# 5_viper_eagle_modern_swleds.net
KiCad netlist of a schematic drawn in Altium Designer
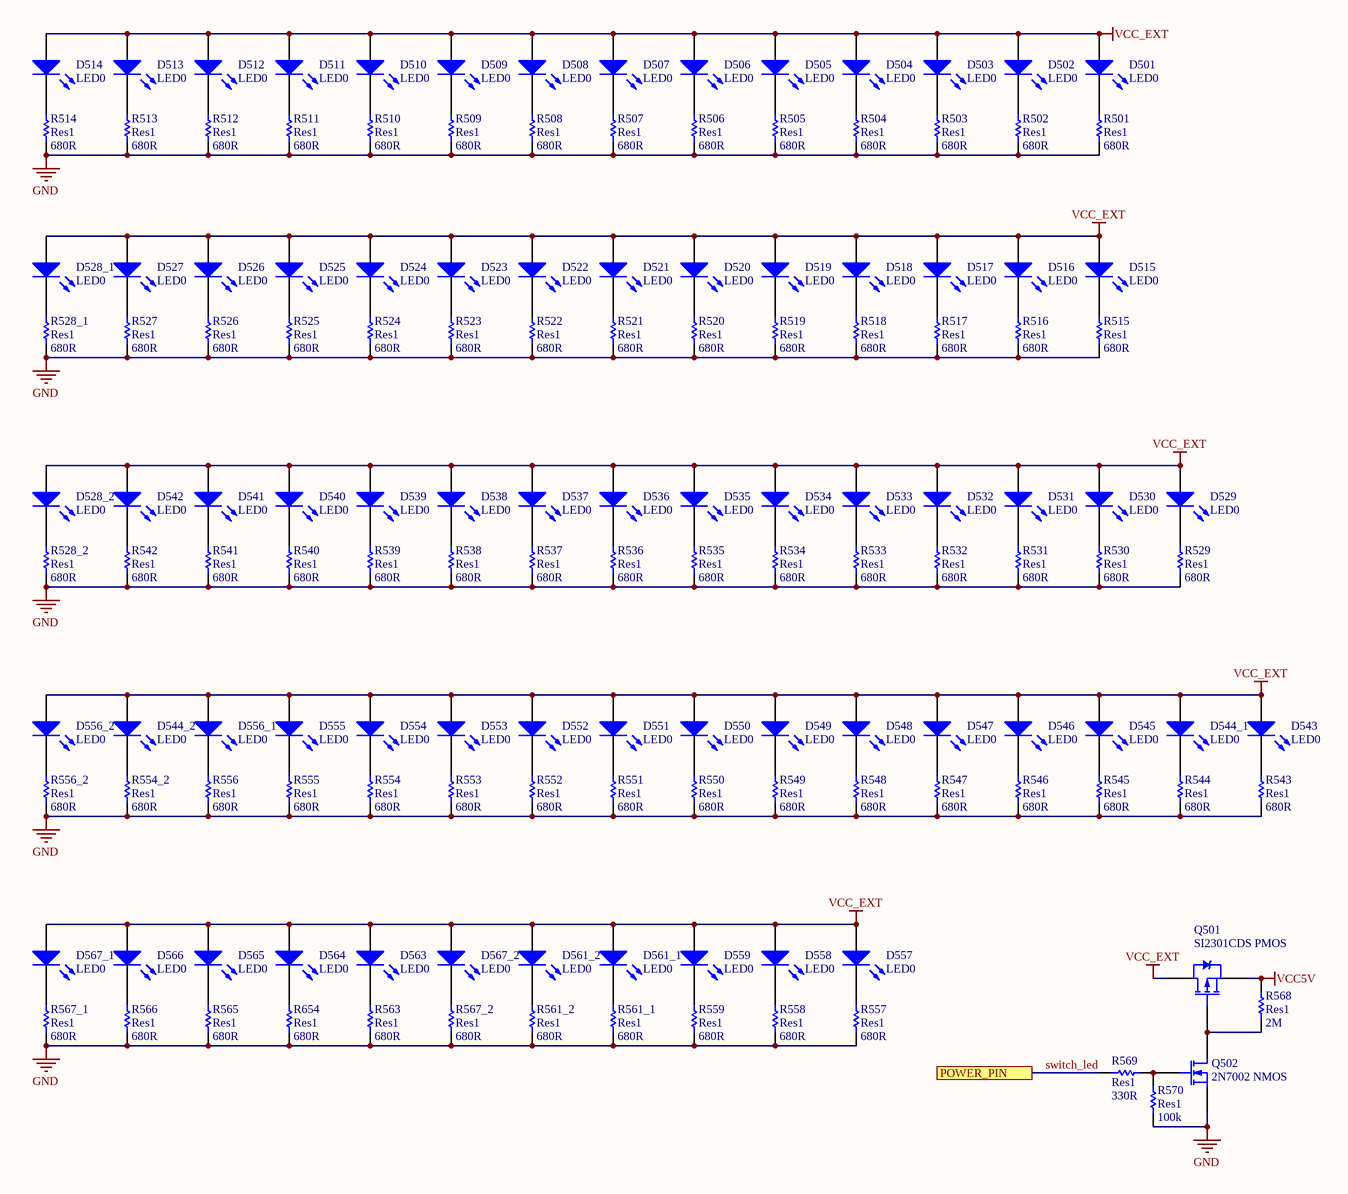
[diagram p0: 5_viper_eagle_modern_swleds.SchDoc]

(export (version "E")
  (design (tool "Eeschema 10.0.6"))
  (components
    (comp (ref "D501")
      (value "LED0")
      (footprint "MX-switch - LED")
      (description "Typical INFRARED GaAs LED")
      (libsource (lib "Miscellaneous Devices") (part "LED0"))
    )
    (comp (ref "D502")
      (value "LED0")
      (footprint "MX-switch - LED")
      (description "Typical INFRARED GaAs LED")
      (libsource (lib "Miscellaneous Devices") (part "LED0"))
    )
    (comp (ref "D503")
      (value "LED0")
      (footprint "MX-switch - LED")
      (description "Typical INFRARED GaAs LED")
      (libsource (lib "Miscellaneous Devices") (part "LED0"))
    )
    (comp (ref "D504")
      (value "LED0")
      (footprint "MX-switch - LED")
      (description "Typical INFRARED GaAs LED")
      (libsource (lib "Miscellaneous Devices") (part "LED0"))
    )
    (comp (ref "D505")
      (value "LED0")
      (footprint "MX-switch - LED")
      (description "Typical INFRARED GaAs LED")
      (libsource (lib "Miscellaneous Devices") (part "LED0"))
    )
    (comp (ref "D506")
      (value "LED0")
      (footprint "MX-switch - LED")
      (description "Typical INFRARED GaAs LED")
      (libsource (lib "Miscellaneous Devices") (part "LED0"))
    )
    (comp (ref "D507")
      (value "LED0")
      (footprint "MX-switch - LED")
      (description "Typical INFRARED GaAs LED")
      (libsource (lib "Miscellaneous Devices") (part "LED0"))
    )
    (comp (ref "D508")
      (value "LED0")
      (footprint "MX-switch - LED")
      (description "Typical INFRARED GaAs LED")
      (libsource (lib "Miscellaneous Devices") (part "LED0"))
    )
    (comp (ref "D509")
      (value "LED0")
      (footprint "MX-switch - LED")
      (description "Typical INFRARED GaAs LED")
      (libsource (lib "Miscellaneous Devices") (part "LED0"))
    )
    (comp (ref "D510")
      (value "LED0")
      (footprint "MX-switch - LED")
      (description "Typical INFRARED GaAs LED")
      (libsource (lib "Miscellaneous Devices") (part "LED0"))
    )
    (comp (ref "D511")
      (value "LED0")
      (footprint "MX-switch - LED")
      (description "Typical INFRARED GaAs LED")
      (libsource (lib "Miscellaneous Devices") (part "LED0"))
    )
    (comp (ref "D512")
      (value "LED0")
      (footprint "MX-switch - LED")
      (description "Typical INFRARED GaAs LED")
      (libsource (lib "Miscellaneous Devices") (part "LED0"))
    )
    (comp (ref "D513")
      (value "LED0")
      (footprint "MX-switch - LED")
      (description "Typical INFRARED GaAs LED")
      (libsource (lib "Miscellaneous Devices") (part "LED0"))
    )
    (comp (ref "D514")
      (value "LED0")
      (footprint "MX-switch - LED")
      (description "Typical INFRARED GaAs LED")
      (libsource (lib "Miscellaneous Devices") (part "LED0"))
    )
    (comp (ref "D515")
      (value "LED0")
      (footprint "MX-switch - LED")
      (description "Typical INFRARED GaAs LED")
      (libsource (lib "Miscellaneous Devices") (part "LED0"))
    )
    (comp (ref "D516")
      (value "LED0")
      (footprint "MX-switch - LED")
      (description "Typical INFRARED GaAs LED")
      (libsource (lib "Miscellaneous Devices") (part "LED0"))
    )
    (comp (ref "D517")
      (value "LED0")
      (footprint "MX-switch - LED")
      (description "Typical INFRARED GaAs LED")
      (libsource (lib "Miscellaneous Devices") (part "LED0"))
    )
    (comp (ref "D518")
      (value "LED0")
      (footprint "MX-switch - LED")
      (description "Typical INFRARED GaAs LED")
      (libsource (lib "Miscellaneous Devices") (part "LED0"))
    )
    (comp (ref "D519")
      (value "LED0")
      (footprint "MX-switch - LED")
      (description "Typical INFRARED GaAs LED")
      (libsource (lib "Miscellaneous Devices") (part "LED0"))
    )
    (comp (ref "D520")
      (value "LED0")
      (footprint "MX-switch - LED")
      (description "Typical INFRARED GaAs LED")
      (libsource (lib "Miscellaneous Devices") (part "LED0"))
    )
    (comp (ref "D521")
      (value "LED0")
      (footprint "MX-switch - LED")
      (description "Typical INFRARED GaAs LED")
      (libsource (lib "Miscellaneous Devices") (part "LED0"))
    )
    (comp (ref "D522")
      (value "LED0")
      (footprint "MX-switch - LED")
      (description "Typical INFRARED GaAs LED")
      (libsource (lib "Miscellaneous Devices") (part "LED0"))
    )
    (comp (ref "D523")
      (value "LED0")
      (footprint "MX-switch - LED")
      (description "Typical INFRARED GaAs LED")
      (libsource (lib "Miscellaneous Devices") (part "LED0"))
    )
    (comp (ref "D524")
      (value "LED0")
      (footprint "MX-switch - LED")
      (description "Typical INFRARED GaAs LED")
      (libsource (lib "Miscellaneous Devices") (part "LED0"))
    )
    (comp (ref "D525")
      (value "LED0")
      (footprint "MX-switch - LED")
      (description "Typical INFRARED GaAs LED")
      (libsource (lib "Miscellaneous Devices") (part "LED0"))
    )
    (comp (ref "D526")
      (value "LED0")
      (footprint "MX-switch - LED")
      (description "Typical INFRARED GaAs LED")
      (libsource (lib "Miscellaneous Devices") (part "LED0"))
    )
    (comp (ref "D527")
      (value "LED0")
      (footprint "MX-switch - LED")
      (description "Typical INFRARED GaAs LED")
      (libsource (lib "Miscellaneous Devices") (part "LED0"))
    )
    (comp (ref "D528_1")
      (value "LED0")
      (footprint "MX-switch - LED")
      (description "Typical INFRARED GaAs LED")
      (libsource (lib "Miscellaneous Devices") (part "LED0"))
    )
    (comp (ref "D528_2")
      (value "LED0")
      (footprint "MX-switch - LED")
      (description "Typical INFRARED GaAs LED")
      (libsource (lib "Miscellaneous Devices") (part "LED0"))
    )
    (comp (ref "D529")
      (value "LED0")
      (footprint "MX-switch - CAPS - LED NO SWITCH")
      (description "Typical INFRARED GaAs LED")
      (libsource (lib "Miscellaneous Devices") (part "LED0"))
    )
    (comp (ref "D530")
      (value "LED0")
      (footprint "MX-switch - LED")
      (description "Typical INFRARED GaAs LED")
      (libsource (lib "Miscellaneous Devices") (part "LED0"))
    )
    (comp (ref "D531")
      (value "LED0")
      (footprint "MX-switch - LED")
      (description "Typical INFRARED GaAs LED")
      (libsource (lib "Miscellaneous Devices") (part "LED0"))
    )
    (comp (ref "D532")
      (value "LED0")
      (footprint "MX-switch - LED")
      (description "Typical INFRARED GaAs LED")
      (libsource (lib "Miscellaneous Devices") (part "LED0"))
    )
    (comp (ref "D533")
      (value "LED0")
      (footprint "MX-switch - LED")
      (description "Typical INFRARED GaAs LED")
      (libsource (lib "Miscellaneous Devices") (part "LED0"))
    )
    (comp (ref "D534")
      (value "LED0")
      (footprint "MX-switch - LED")
      (description "Typical INFRARED GaAs LED")
      (libsource (lib "Miscellaneous Devices") (part "LED0"))
    )
    (comp (ref "D535")
      (value "LED0")
      (footprint "MX-switch - LED")
      (description "Typical INFRARED GaAs LED")
      (libsource (lib "Miscellaneous Devices") (part "LED0"))
    )
    (comp (ref "D536")
      (value "LED0")
      (footprint "MX-switch - LED")
      (description "Typical INFRARED GaAs LED")
      (libsource (lib "Miscellaneous Devices") (part "LED0"))
    )
    (comp (ref "D537")
      (value "LED0")
      (footprint "MX-switch - LED")
      (description "Typical INFRARED GaAs LED")
      (libsource (lib "Miscellaneous Devices") (part "LED0"))
    )
    (comp (ref "D538")
      (value "LED0")
      (footprint "MX-switch - LED")
      (description "Typical INFRARED GaAs LED")
      (libsource (lib "Miscellaneous Devices") (part "LED0"))
    )
    (comp (ref "D539")
      (value "LED0")
      (footprint "MX-switch - LED")
      (description "Typical INFRARED GaAs LED")
      (libsource (lib "Miscellaneous Devices") (part "LED0"))
    )
    (comp (ref "D540")
      (value "LED0")
      (footprint "MX-switch - LED")
      (description "Typical INFRARED GaAs LED")
      (libsource (lib "Miscellaneous Devices") (part "LED0"))
    )
    (comp (ref "D541")
      (value "LED0")
      (footprint "MX-switch - LED")
      (description "Typical INFRARED GaAs LED")
      (libsource (lib "Miscellaneous Devices") (part "LED0"))
    )
    (comp (ref "D542")
      (value "LED0")
      (footprint "MX-switch - LED")
      (description "Typical INFRARED GaAs LED")
      (libsource (lib "Miscellaneous Devices") (part "LED0"))
    )
    (comp (ref "D543")
      (value "LED0")
      (footprint "MX-switch - LED")
      (description "Typical INFRARED GaAs LED")
      (libsource (lib "Miscellaneous Devices") (part "LED0"))
    )
    (comp (ref "D544_1")
      (value "LED0")
      (footprint "MX-switch - LED")
      (description "Typical INFRARED GaAs LED")
      (libsource (lib "Miscellaneous Devices") (part "LED0"))
    )
    (comp (ref "D544_2")
      (value "LED0")
      (footprint "MX-switch - LED")
      (description "Typical INFRARED GaAs LED")
      (libsource (lib "Miscellaneous Devices") (part "LED0"))
    )
    (comp (ref "D545")
      (value "LED0")
      (footprint "MX-switch - LED")
      (description "Typical INFRARED GaAs LED")
      (libsource (lib "Miscellaneous Devices") (part "LED0"))
    )
    (comp (ref "D546")
      (value "LED0")
      (footprint "MX-switch - LED")
      (description "Typical INFRARED GaAs LED")
      (libsource (lib "Miscellaneous Devices") (part "LED0"))
    )
    (comp (ref "D547")
      (value "LED0")
      (footprint "MX-switch - LED")
      (description "Typical INFRARED GaAs LED")
      (libsource (lib "Miscellaneous Devices") (part "LED0"))
    )
    (comp (ref "D548")
      (value "LED0")
      (footprint "MX-switch - LED")
      (description "Typical INFRARED GaAs LED")
      (libsource (lib "Miscellaneous Devices") (part "LED0"))
    )
    (comp (ref "D549")
      (value "LED0")
      (footprint "MX-switch - LED")
      (description "Typical INFRARED GaAs LED")
      (libsource (lib "Miscellaneous Devices") (part "LED0"))
    )
    (comp (ref "D550")
      (value "LED0")
      (footprint "MX-switch - LED")
      (description "Typical INFRARED GaAs LED")
      (libsource (lib "Miscellaneous Devices") (part "LED0"))
    )
    (comp (ref "D551")
      (value "LED0")
      (footprint "MX-switch - LED")
      (description "Typical INFRARED GaAs LED")
      (libsource (lib "Miscellaneous Devices") (part "LED0"))
    )
    (comp (ref "D552")
      (value "LED0")
      (footprint "MX-switch - LED")
      (description "Typical INFRARED GaAs LED")
      (libsource (lib "Miscellaneous Devices") (part "LED0"))
    )
    (comp (ref "D553")
      (value "LED0")
      (footprint "MX-switch - LED")
      (description "Typical INFRARED GaAs LED")
      (libsource (lib "Miscellaneous Devices") (part "LED0"))
    )
    (comp (ref "D554")
      (value "LED0")
      (footprint "MX-switch - LED")
      (description "Typical INFRARED GaAs LED")
      (libsource (lib "Miscellaneous Devices") (part "LED0"))
    )
    (comp (ref "D555")
      (value "LED0")
      (footprint "MX-switch - LED")
      (description "Typical INFRARED GaAs LED")
      (libsource (lib "Miscellaneous Devices") (part "LED0"))
    )
    (comp (ref "D556_1")
      (value "LED0")
      (footprint "MX-switch - LED")
      (description "Typical INFRARED GaAs LED")
      (libsource (lib "Miscellaneous Devices") (part "LED0"))
    )
    (comp (ref "D556_2")
      (value "LED0")
      (footprint "MX-switch - LED")
      (description "Typical INFRARED GaAs LED")
      (libsource (lib "Miscellaneous Devices") (part "LED0"))
    )
    (comp (ref "D557")
      (value "LED0")
      (footprint "MX-switch - LED - MODS")
      (description "Typical INFRARED GaAs LED")
      (libsource (lib "Miscellaneous Devices") (part "LED0"))
    )
    (comp (ref "D558")
      (value "LED0")
      (footprint "MX-switch - LED - MODS")
      (description "Typical INFRARED GaAs LED")
      (libsource (lib "Miscellaneous Devices") (part "LED0"))
    )
    (comp (ref "D559")
      (value "LED0")
      (footprint "MX-switch - LED - MODS")
      (description "Typical INFRARED GaAs LED")
      (libsource (lib "Miscellaneous Devices") (part "LED0"))
    )
    (comp (ref "D561_1")
      (value "LED0")
      (footprint "MX-switch - LED")
      (description "Typical INFRARED GaAs LED")
      (libsource (lib "Miscellaneous Devices") (part "LED0"))
    )
    (comp (ref "D561_2")
      (value "LED0")
      (footprint "MX-switch - LED")
      (description "Typical INFRARED GaAs LED")
      (libsource (lib "Miscellaneous Devices") (part "LED0"))
    )
    (comp (ref "D563")
      (value "LED0")
      (footprint "MX-switch - LED")
      (description "Typical INFRARED GaAs LED")
      (libsource (lib "Miscellaneous Devices") (part "LED0"))
    )
    (comp (ref "D564")
      (value "LED0")
      (footprint "MX-switch - LED - MODS")
      (description "Typical INFRARED GaAs LED")
      (libsource (lib "Miscellaneous Devices") (part "LED0"))
    )
    (comp (ref "D565")
      (value "LED0")
      (footprint "MX-switch - LED - MODS")
      (description "Typical INFRARED GaAs LED")
      (libsource (lib "Miscellaneous Devices") (part "LED0"))
    )
    (comp (ref "D566")
      (value "LED0")
      (footprint "MX-switch - LED - MODS")
      (description "Typical INFRARED GaAs LED")
      (libsource (lib "Miscellaneous Devices") (part "LED0"))
    )
    (comp (ref "D567_1")
      (value "LED0")
      (footprint "MX-switch - LED")
      (description "Typical INFRARED GaAs LED")
      (libsource (lib "Miscellaneous Devices") (part "LED0"))
    )
    (comp (ref "D567_2")
      (value "LED0")
      (footprint "MX-switch - LED")
      (description "Typical INFRARED GaAs LED")
      (libsource (lib "Miscellaneous Devices") (part "LED0"))
    )
    (comp (ref "Q501")
      (value "SI2301CDS PMOS")
      (footprint "SOT-23-3")
      (description "P-Channel Power MOSFET")
      (fields (field (name "MRF.PART") "SI2301CDS-T1-GE3") (field (name "LCSC PART #") "C10487"))
      (libsource (lib "Miscellaneous Devices") (part "PMOS-2"))
    )
    (comp (ref "Q502")
      (value "2N7002 NMOS")
      (footprint "SOT-23-3")
      (description "N-Channel MOSFET")
      (fields (field (name "LCSC PART #") "C8545") (field (name "MRF.PART") "2N7002"))
      (libsource (lib "Miscellaneous Devices") (part "MOSFET-N"))
    )
    (comp (ref "R501")
      (value "Res1")
      (footprint "R0603[1608]")
      (description "Resistor")
      (fields
        (field (name "ALTIUM_VALUE") "680R")
        (field (name "LCSC PART #") "C23228")
        (field (name "MRF.PART") "0603WAF6800T5E")
      )
      (libsource (lib "Miscellaneous Devices") (part "Res1"))
    )
    (comp (ref "R502")
      (value "Res1")
      (footprint "R0603[1608]")
      (description "Resistor")
      (fields
        (field (name "ALTIUM_VALUE") "680R")
        (field (name "LCSC PART #") "C23228")
        (field (name "MRF.PART") "0603WAF6800T5E")
      )
      (libsource (lib "Miscellaneous Devices") (part "Res1"))
    )
    (comp (ref "R503")
      (value "Res1")
      (footprint "R0603[1608]")
      (description "Resistor")
      (fields
        (field (name "ALTIUM_VALUE") "680R")
        (field (name "LCSC PART #") "C23228")
        (field (name "MRF.PART") "0603WAF6800T5E")
      )
      (libsource (lib "Miscellaneous Devices") (part "Res1"))
    )
    (comp (ref "R504")
      (value "Res1")
      (footprint "R0603[1608]")
      (description "Resistor")
      (fields
        (field (name "ALTIUM_VALUE") "680R")
        (field (name "LCSC PART #") "C23228")
        (field (name "MRF.PART") "0603WAF6800T5E")
      )
      (libsource (lib "Miscellaneous Devices") (part "Res1"))
    )
    (comp (ref "R505")
      (value "Res1")
      (footprint "R0603[1608]")
      (description "Resistor")
      (fields
        (field (name "ALTIUM_VALUE") "680R")
        (field (name "LCSC PART #") "C23228")
        (field (name "MRF.PART") "0603WAF6800T5E")
      )
      (libsource (lib "Miscellaneous Devices") (part "Res1"))
    )
    (comp (ref "R506")
      (value "Res1")
      (footprint "R0603[1608]")
      (description "Resistor")
      (fields
        (field (name "ALTIUM_VALUE") "680R")
        (field (name "LCSC PART #") "C23228")
        (field (name "MRF.PART") "0603WAF6800T5E")
      )
      (libsource (lib "Miscellaneous Devices") (part "Res1"))
    )
    (comp (ref "R507")
      (value "Res1")
      (footprint "R0603[1608]")
      (description "Resistor")
      (fields
        (field (name "ALTIUM_VALUE") "680R")
        (field (name "LCSC PART #") "C23228")
        (field (name "MRF.PART") "0603WAF6800T5E")
      )
      (libsource (lib "Miscellaneous Devices") (part "Res1"))
    )
    (comp (ref "R508")
      (value "Res1")
      (footprint "R0603[1608]")
      (description "Resistor")
      (fields
        (field (name "ALTIUM_VALUE") "680R")
        (field (name "LCSC PART #") "C23228")
        (field (name "MRF.PART") "0603WAF6800T5E")
      )
      (libsource (lib "Miscellaneous Devices") (part "Res1"))
    )
    (comp (ref "R509")
      (value "Res1")
      (footprint "R0603[1608]")
      (description "Resistor")
      (fields
        (field (name "ALTIUM_VALUE") "680R")
        (field (name "LCSC PART #") "C23228")
        (field (name "MRF.PART") "0603WAF6800T5E")
      )
      (libsource (lib "Miscellaneous Devices") (part "Res1"))
    )
    (comp (ref "R510")
      (value "Res1")
      (footprint "R0603[1608]")
      (description "Resistor")
      (fields
        (field (name "ALTIUM_VALUE") "680R")
        (field (name "LCSC PART #") "C23228")
        (field (name "MRF.PART") "0603WAF6800T5E")
      )
      (libsource (lib "Miscellaneous Devices") (part "Res1"))
    )
    (comp (ref "R511")
      (value "Res1")
      (footprint "R0603[1608]")
      (description "Resistor")
      (fields
        (field (name "ALTIUM_VALUE") "680R")
        (field (name "LCSC PART #") "C23228")
        (field (name "MRF.PART") "0603WAF6800T5E")
      )
      (libsource (lib "Miscellaneous Devices") (part "Res1"))
    )
    (comp (ref "R512")
      (value "Res1")
      (footprint "R0603[1608]")
      (description "Resistor")
      (fields
        (field (name "ALTIUM_VALUE") "680R")
        (field (name "LCSC PART #") "C23228")
        (field (name "MRF.PART") "0603WAF6800T5E")
      )
      (libsource (lib "Miscellaneous Devices") (part "Res1"))
    )
    (comp (ref "R513")
      (value "Res1")
      (footprint "R0603[1608]")
      (description "Resistor")
      (fields
        (field (name "ALTIUM_VALUE") "680R")
        (field (name "LCSC PART #") "C23228")
        (field (name "MRF.PART") "0603WAF6800T5E")
      )
      (libsource (lib "Miscellaneous Devices") (part "Res1"))
    )
    (comp (ref "R514")
      (value "Res1")
      (footprint "R0603[1608]")
      (description "Resistor")
      (fields
        (field (name "ALTIUM_VALUE") "680R")
        (field (name "LCSC PART #") "C23228")
        (field (name "MRF.PART") "0603WAF6800T5E")
      )
      (libsource (lib "Miscellaneous Devices") (part "Res1"))
    )
    (comp (ref "R515")
      (value "Res1")
      (footprint "R0603[1608]")
      (description "Resistor")
      (fields
        (field (name "ALTIUM_VALUE") "680R")
        (field (name "LCSC PART #") "C23228")
        (field (name "MRF.PART") "0603WAF6800T5E")
      )
      (libsource (lib "Miscellaneous Devices") (part "Res1"))
    )
    (comp (ref "R516")
      (value "Res1")
      (footprint "R0603[1608]")
      (description "Resistor")
      (fields
        (field (name "ALTIUM_VALUE") "680R")
        (field (name "LCSC PART #") "C23228")
        (field (name "MRF.PART") "0603WAF6800T5E")
      )
      (libsource (lib "Miscellaneous Devices") (part "Res1"))
    )
    (comp (ref "R517")
      (value "Res1")
      (footprint "R0603[1608]")
      (description "Resistor")
      (fields
        (field (name "ALTIUM_VALUE") "680R")
        (field (name "LCSC PART #") "C23228")
        (field (name "MRF.PART") "0603WAF6800T5E")
      )
      (libsource (lib "Miscellaneous Devices") (part "Res1"))
    )
    (comp (ref "R518")
      (value "Res1")
      (footprint "R0603[1608]")
      (description "Resistor")
      (fields
        (field (name "ALTIUM_VALUE") "680R")
        (field (name "LCSC PART #") "C23228")
        (field (name "MRF.PART") "0603WAF6800T5E")
      )
      (libsource (lib "Miscellaneous Devices") (part "Res1"))
    )
    (comp (ref "R519")
      (value "Res1")
      (footprint "R0603[1608]")
      (description "Resistor")
      (fields
        (field (name "ALTIUM_VALUE") "680R")
        (field (name "LCSC PART #") "C23228")
        (field (name "MRF.PART") "0603WAF6800T5E")
      )
      (libsource (lib "Miscellaneous Devices") (part "Res1"))
    )
    (comp (ref "R520")
      (value "Res1")
      (footprint "R0603[1608]")
      (description "Resistor")
      (fields
        (field (name "ALTIUM_VALUE") "680R")
        (field (name "LCSC PART #") "C23228")
        (field (name "MRF.PART") "0603WAF6800T5E")
      )
      (libsource (lib "Miscellaneous Devices") (part "Res1"))
    )
    (comp (ref "R521")
      (value "Res1")
      (footprint "R0603[1608]")
      (description "Resistor")
      (fields
        (field (name "ALTIUM_VALUE") "680R")
        (field (name "LCSC PART #") "C23228")
        (field (name "MRF.PART") "0603WAF6800T5E")
      )
      (libsource (lib "Miscellaneous Devices") (part "Res1"))
    )
    (comp (ref "R522")
      (value "Res1")
      (footprint "R0603[1608]")
      (description "Resistor")
      (fields
        (field (name "ALTIUM_VALUE") "680R")
        (field (name "LCSC PART #") "C23228")
        (field (name "MRF.PART") "0603WAF6800T5E")
      )
      (libsource (lib "Miscellaneous Devices") (part "Res1"))
    )
    (comp (ref "R523")
      (value "Res1")
      (footprint "R0603[1608]")
      (description "Resistor")
      (fields
        (field (name "ALTIUM_VALUE") "680R")
        (field (name "LCSC PART #") "C23228")
        (field (name "MRF.PART") "0603WAF6800T5E")
      )
      (libsource (lib "Miscellaneous Devices") (part "Res1"))
    )
    (comp (ref "R524")
      (value "Res1")
      (footprint "R0603[1608]")
      (description "Resistor")
      (fields
        (field (name "ALTIUM_VALUE") "680R")
        (field (name "LCSC PART #") "C23228")
        (field (name "MRF.PART") "0603WAF6800T5E")
      )
      (libsource (lib "Miscellaneous Devices") (part "Res1"))
    )
    (comp (ref "R525")
      (value "Res1")
      (footprint "R0603[1608]")
      (description "Resistor")
      (fields
        (field (name "ALTIUM_VALUE") "680R")
        (field (name "LCSC PART #") "C23228")
        (field (name "MRF.PART") "0603WAF6800T5E")
      )
      (libsource (lib "Miscellaneous Devices") (part "Res1"))
    )
    (comp (ref "R526")
      (value "Res1")
      (footprint "R0603[1608]")
      (description "Resistor")
      (fields
        (field (name "ALTIUM_VALUE") "680R")
        (field (name "LCSC PART #") "C23228")
        (field (name "MRF.PART") "0603WAF6800T5E")
      )
      (libsource (lib "Miscellaneous Devices") (part "Res1"))
    )
    (comp (ref "R527")
      (value "Res1")
      (footprint "R0603[1608]")
      (description "Resistor")
      (fields
        (field (name "ALTIUM_VALUE") "680R")
        (field (name "LCSC PART #") "C23228")
        (field (name "MRF.PART") "0603WAF6800T5E")
      )
      (libsource (lib "Miscellaneous Devices") (part "Res1"))
    )
    (comp (ref "R528_1")
      (value "Res1")
      (footprint "R0603[1608]")
      (description "Resistor")
      (fields
        (field (name "ALTIUM_VALUE") "680R")
        (field (name "LCSC PART #") "C23228")
        (field (name "MRF.PART") "0603WAF6800T5E")
      )
      (libsource (lib "Miscellaneous Devices") (part "Res1"))
    )
    (comp (ref "R528_2")
      (value "Res1")
      (footprint "R0603[1608]")
      (description "Resistor")
      (fields
        (field (name "ALTIUM_VALUE") "680R")
        (field (name "LCSC PART #") "C23228")
        (field (name "MRF.PART") "0603WAF6800T5E")
      )
      (libsource (lib "Miscellaneous Devices") (part "Res1"))
    )
    (comp (ref "R529")
      (value "Res1")
      (footprint "R0603[1608]")
      (description "Resistor")
      (fields
        (field (name "ALTIUM_VALUE") "680R")
        (field (name "LCSC PART #") "C23228")
        (field (name "MRF.PART") "0603WAF6800T5E")
      )
      (libsource (lib "Miscellaneous Devices") (part "Res1"))
    )
    (comp (ref "R530")
      (value "Res1")
      (footprint "R0603[1608]")
      (description "Resistor")
      (fields
        (field (name "ALTIUM_VALUE") "680R")
        (field (name "LCSC PART #") "C23228")
        (field (name "MRF.PART") "0603WAF6800T5E")
      )
      (libsource (lib "Miscellaneous Devices") (part "Res1"))
    )
    (comp (ref "R531")
      (value "Res1")
      (footprint "R0603[1608]")
      (description "Resistor")
      (fields
        (field (name "ALTIUM_VALUE") "680R")
        (field (name "LCSC PART #") "C23228")
        (field (name "MRF.PART") "0603WAF6800T5E")
      )
      (libsource (lib "Miscellaneous Devices") (part "Res1"))
    )
    (comp (ref "R532")
      (value "Res1")
      (footprint "R0603[1608]")
      (description "Resistor")
      (fields
        (field (name "ALTIUM_VALUE") "680R")
        (field (name "LCSC PART #") "C23228")
        (field (name "MRF.PART") "0603WAF6800T5E")
      )
      (libsource (lib "Miscellaneous Devices") (part "Res1"))
    )
    (comp (ref "R533")
      (value "Res1")
      (footprint "R0603[1608]")
      (description "Resistor")
      (fields
        (field (name "ALTIUM_VALUE") "680R")
        (field (name "LCSC PART #") "C23228")
        (field (name "MRF.PART") "0603WAF6800T5E")
      )
      (libsource (lib "Miscellaneous Devices") (part "Res1"))
    )
    (comp (ref "R534")
      (value "Res1")
      (footprint "R0603[1608]")
      (description "Resistor")
      (fields
        (field (name "ALTIUM_VALUE") "680R")
        (field (name "LCSC PART #") "C23228")
        (field (name "MRF.PART") "0603WAF6800T5E")
      )
      (libsource (lib "Miscellaneous Devices") (part "Res1"))
    )
    (comp (ref "R535")
      (value "Res1")
      (footprint "R0603[1608]")
      (description "Resistor")
      (fields
        (field (name "ALTIUM_VALUE") "680R")
        (field (name "LCSC PART #") "C23228")
        (field (name "MRF.PART") "0603WAF6800T5E")
      )
      (libsource (lib "Miscellaneous Devices") (part "Res1"))
    )
    (comp (ref "R536")
      (value "Res1")
      (footprint "R0603[1608]")
      (description "Resistor")
      (fields
        (field (name "ALTIUM_VALUE") "680R")
        (field (name "LCSC PART #") "C23228")
        (field (name "MRF.PART") "0603WAF6800T5E")
      )
      (libsource (lib "Miscellaneous Devices") (part "Res1"))
    )
    (comp (ref "R537")
      (value "Res1")
      (footprint "R0603[1608]")
      (description "Resistor")
      (fields
        (field (name "ALTIUM_VALUE") "680R")
        (field (name "LCSC PART #") "C23228")
        (field (name "MRF.PART") "0603WAF6800T5E")
      )
      (libsource (lib "Miscellaneous Devices") (part "Res1"))
    )
    (comp (ref "R538")
      (value "Res1")
      (footprint "R0603[1608]")
      (description "Resistor")
      (fields
        (field (name "ALTIUM_VALUE") "680R")
        (field (name "LCSC PART #") "C23228")
        (field (name "MRF.PART") "0603WAF6800T5E")
      )
      (libsource (lib "Miscellaneous Devices") (part "Res1"))
    )
    (comp (ref "R539")
      (value "Res1")
      (footprint "R0603[1608]")
      (description "Resistor")
      (fields
        (field (name "ALTIUM_VALUE") "680R")
        (field (name "LCSC PART #") "C23228")
        (field (name "MRF.PART") "0603WAF6800T5E")
      )
      (libsource (lib "Miscellaneous Devices") (part "Res1"))
    )
    (comp (ref "R540")
      (value "Res1")
      (footprint "R0603[1608]")
      (description "Resistor")
      (fields
        (field (name "ALTIUM_VALUE") "680R")
        (field (name "LCSC PART #") "C23228")
        (field (name "MRF.PART") "0603WAF6800T5E")
      )
      (libsource (lib "Miscellaneous Devices") (part "Res1"))
    )
    (comp (ref "R541")
      (value "Res1")
      (footprint "R0603[1608]")
      (description "Resistor")
      (fields
        (field (name "ALTIUM_VALUE") "680R")
        (field (name "LCSC PART #") "C23228")
        (field (name "MRF.PART") "0603WAF6800T5E")
      )
      (libsource (lib "Miscellaneous Devices") (part "Res1"))
    )
    (comp (ref "R542")
      (value "Res1")
      (footprint "R0603[1608]")
      (description "Resistor")
      (fields
        (field (name "ALTIUM_VALUE") "680R")
        (field (name "LCSC PART #") "C23228")
        (field (name "MRF.PART") "0603WAF6800T5E")
      )
      (libsource (lib "Miscellaneous Devices") (part "Res1"))
    )
    (comp (ref "R543")
      (value "Res1")
      (footprint "R0603[1608]")
      (description "Resistor")
      (fields
        (field (name "ALTIUM_VALUE") "680R")
        (field (name "LCSC PART #") "C23228")
        (field (name "MRF.PART") "0603WAF6800T5E")
      )
      (libsource (lib "Miscellaneous Devices") (part "Res1"))
    )
    (comp (ref "R544")
      (value "Res1")
      (footprint "R0603[1608]")
      (description "Resistor")
      (fields
        (field (name "ALTIUM_VALUE") "680R")
        (field (name "LCSC PART #") "C23228")
        (field (name "MRF.PART") "0603WAF6800T5E")
      )
      (libsource (lib "Miscellaneous Devices") (part "Res1"))
    )
    (comp (ref "R545")
      (value "Res1")
      (footprint "R0603[1608]")
      (description "Resistor")
      (fields
        (field (name "ALTIUM_VALUE") "680R")
        (field (name "LCSC PART #") "C23228")
        (field (name "MRF.PART") "0603WAF6800T5E")
      )
      (libsource (lib "Miscellaneous Devices") (part "Res1"))
    )
    (comp (ref "R546")
      (value "Res1")
      (footprint "R0603[1608]")
      (description "Resistor")
      (fields
        (field (name "ALTIUM_VALUE") "680R")
        (field (name "LCSC PART #") "C23228")
        (field (name "MRF.PART") "0603WAF6800T5E")
      )
      (libsource (lib "Miscellaneous Devices") (part "Res1"))
    )
    (comp (ref "R547")
      (value "Res1")
      (footprint "R0603[1608]")
      (description "Resistor")
      (fields
        (field (name "ALTIUM_VALUE") "680R")
        (field (name "LCSC PART #") "C23228")
        (field (name "MRF.PART") "0603WAF6800T5E")
      )
      (libsource (lib "Miscellaneous Devices") (part "Res1"))
    )
    (comp (ref "R548")
      (value "Res1")
      (footprint "R0603[1608]")
      (description "Resistor")
      (fields
        (field (name "ALTIUM_VALUE") "680R")
        (field (name "LCSC PART #") "C23228")
        (field (name "MRF.PART") "0603WAF6800T5E")
      )
      (libsource (lib "Miscellaneous Devices") (part "Res1"))
    )
    (comp (ref "R549")
      (value "Res1")
      (footprint "R0603[1608]")
      (description "Resistor")
      (fields
        (field (name "ALTIUM_VALUE") "680R")
        (field (name "LCSC PART #") "C23228")
        (field (name "MRF.PART") "0603WAF6800T5E")
      )
      (libsource (lib "Miscellaneous Devices") (part "Res1"))
    )
    (comp (ref "R550")
      (value "Res1")
      (footprint "R0603[1608]")
      (description "Resistor")
      (fields
        (field (name "ALTIUM_VALUE") "680R")
        (field (name "LCSC PART #") "C23228")
        (field (name "MRF.PART") "0603WAF6800T5E")
      )
      (libsource (lib "Miscellaneous Devices") (part "Res1"))
    )
    (comp (ref "R551")
      (value "Res1")
      (footprint "R0603[1608]")
      (description "Resistor")
      (fields
        (field (name "ALTIUM_VALUE") "680R")
        (field (name "LCSC PART #") "C23228")
        (field (name "MRF.PART") "0603WAF6800T5E")
      )
      (libsource (lib "Miscellaneous Devices") (part "Res1"))
    )
    (comp (ref "R552")
      (value "Res1")
      (footprint "R0603[1608]")
      (description "Resistor")
      (fields
        (field (name "ALTIUM_VALUE") "680R")
        (field (name "LCSC PART #") "C23228")
        (field (name "MRF.PART") "0603WAF6800T5E")
      )
      (libsource (lib "Miscellaneous Devices") (part "Res1"))
    )
    (comp (ref "R553")
      (value "Res1")
      (footprint "R0603[1608]")
      (description "Resistor")
      (fields
        (field (name "ALTIUM_VALUE") "680R")
        (field (name "LCSC PART #") "C23228")
        (field (name "MRF.PART") "0603WAF6800T5E")
      )
      (libsource (lib "Miscellaneous Devices") (part "Res1"))
    )
    (comp (ref "R554")
      (value "Res1")
      (footprint "R0603[1608]")
      (description "Resistor")
      (fields
        (field (name "ALTIUM_VALUE") "680R")
        (field (name "LCSC PART #") "C23228")
        (field (name "MRF.PART") "0603WAF6800T5E")
      )
      (libsource (lib "Miscellaneous Devices") (part "Res1"))
    )
    (comp (ref "R554_2")
      (value "Res1")
      (footprint "R0603[1608]")
      (description "Resistor")
      (fields
        (field (name "ALTIUM_VALUE") "680R")
        (field (name "LCSC PART #") "C23228")
        (field (name "MRF.PART") "0603WAF6800T5E")
      )
      (libsource (lib "Miscellaneous Devices") (part "Res1"))
    )
    (comp (ref "R555")
      (value "Res1")
      (footprint "R0603[1608]")
      (description "Resistor")
      (fields
        (field (name "ALTIUM_VALUE") "680R")
        (field (name "LCSC PART #") "C23228")
        (field (name "MRF.PART") "0603WAF6800T5E")
      )
      (libsource (lib "Miscellaneous Devices") (part "Res1"))
    )
    (comp (ref "R556")
      (value "Res1")
      (footprint "R0603[1608]")
      (description "Resistor")
      (fields
        (field (name "ALTIUM_VALUE") "680R")
        (field (name "LCSC PART #") "C23228")
        (field (name "MRF.PART") "0603WAF6800T5E")
      )
      (libsource (lib "Miscellaneous Devices") (part "Res1"))
    )
    (comp (ref "R556_2")
      (value "Res1")
      (footprint "R0603[1608]")
      (description "Resistor")
      (fields
        (field (name "ALTIUM_VALUE") "680R")
        (field (name "LCSC PART #") "C23228")
        (field (name "MRF.PART") "0603WAF6800T5E")
      )
      (libsource (lib "Miscellaneous Devices") (part "Res1"))
    )
    (comp (ref "R557")
      (value "Res1")
      (footprint "R0603[1608]")
      (description "Resistor")
      (fields
        (field (name "ALTIUM_VALUE") "680R")
        (field (name "LCSC PART #") "C23228")
        (field (name "MRF.PART") "0603WAF6800T5E")
      )
      (libsource (lib "Miscellaneous Devices") (part "Res1"))
    )
    (comp (ref "R558")
      (value "Res1")
      (footprint "R0603[1608]")
      (description "Resistor")
      (fields
        (field (name "ALTIUM_VALUE") "680R")
        (field (name "LCSC PART #") "C23228")
        (field (name "MRF.PART") "0603WAF6800T5E")
      )
      (libsource (lib "Miscellaneous Devices") (part "Res1"))
    )
    (comp (ref "R559")
      (value "Res1")
      (footprint "R0603[1608]")
      (description "Resistor")
      (fields
        (field (name "ALTIUM_VALUE") "680R")
        (field (name "LCSC PART #") "C23228")
        (field (name "MRF.PART") "0603WAF6800T5E")
      )
      (libsource (lib "Miscellaneous Devices") (part "Res1"))
    )
    (comp (ref "R561_1")
      (value "Res1")
      (footprint "R0603[1608]")
      (description "Resistor")
      (fields
        (field (name "ALTIUM_VALUE") "680R")
        (field (name "LCSC PART #") "C23228")
        (field (name "MRF.PART") "0603WAF6800T5E")
      )
      (libsource (lib "Miscellaneous Devices") (part "Res1"))
    )
    (comp (ref "R561_2")
      (value "Res1")
      (footprint "R0603[1608]")
      (description "Resistor")
      (fields
        (field (name "ALTIUM_VALUE") "680R")
        (field (name "LCSC PART #") "C23228")
        (field (name "MRF.PART") "0603WAF6800T5E")
      )
      (libsource (lib "Miscellaneous Devices") (part "Res1"))
    )
    (comp (ref "R563")
      (value "Res1")
      (footprint "R0603[1608]")
      (description "Resistor")
      (fields
        (field (name "ALTIUM_VALUE") "680R")
        (field (name "LCSC PART #") "C23228")
        (field (name "MRF.PART") "0603WAF6800T5E")
      )
      (libsource (lib "Miscellaneous Devices") (part "Res1"))
    )
    (comp (ref "R565")
      (value "Res1")
      (footprint "R0603[1608]")
      (description "Resistor")
      (fields
        (field (name "ALTIUM_VALUE") "680R")
        (field (name "LCSC PART #") "C23228")
        (field (name "MRF.PART") "0603WAF6800T5E")
      )
      (libsource (lib "Miscellaneous Devices") (part "Res1"))
    )
    (comp (ref "R566")
      (value "Res1")
      (footprint "R0603[1608]")
      (description "Resistor")
      (fields
        (field (name "ALTIUM_VALUE") "680R")
        (field (name "LCSC PART #") "C23228")
        (field (name "MRF.PART") "0603WAF6800T5E")
      )
      (libsource (lib "Miscellaneous Devices") (part "Res1"))
    )
    (comp (ref "R567_1")
      (value "Res1")
      (footprint "R0603[1608]")
      (description "Resistor")
      (fields
        (field (name "ALTIUM_VALUE") "680R")
        (field (name "LCSC PART #") "C23228")
        (field (name "MRF.PART") "0603WAF6800T5E")
      )
      (libsource (lib "Miscellaneous Devices") (part "Res1"))
    )
    (comp (ref "R567_2")
      (value "Res1")
      (footprint "R0603[1608]")
      (description "Resistor")
      (fields
        (field (name "ALTIUM_VALUE") "680R")
        (field (name "LCSC PART #") "C23228")
        (field (name "MRF.PART") "0603WAF6800T5E")
      )
      (libsource (lib "Miscellaneous Devices") (part "Res1"))
    )
    (comp (ref "R568")
      (value "Res1")
      (footprint "R0603[1608]")
      (description "Resistor")
      (fields
        (field (name "ALTIUM_VALUE") "2M")
        (field (name "MRF.PART") "0603WAF2004T5E")
        (field (name "LCSC PART #") "C22976")
      )
      (libsource (lib "Miscellaneous Devices") (part "Res1"))
    )
    (comp (ref "R569")
      (value "Res1")
      (footprint "R0603[1608]")
      (description "Resistor")
      (fields
        (field (name "ALTIUM_VALUE") "330R")
        (field (name "LCSC PART #") "C23138")
        (field (name "MRF.PART") "0603WAF3300T5E")
      )
      (libsource (lib "Miscellaneous Devices") (part "Res1"))
    )
    (comp (ref "R570")
      (value "Res1")
      (footprint "R0603[1608]")
      (description "Resistor")
      (fields
        (field (name "ALTIUM_VALUE") "100k")
        (field (name "MRF.PART") "0603WAF1003T5E")
        (field (name "LCSC PART #") "C25803")
      )
      (libsource (lib "Miscellaneous Devices") (part "Res1"))
    )
    (comp (ref "R654")
      (value "Res1")
      (footprint "R0603[1608]")
      (description "Resistor")
      (fields
        (field (name "ALTIUM_VALUE") "680R")
        (field (name "LCSC PART #") "C23228")
        (field (name "MRF.PART") "0603WAF6800T5E")
      )
      (libsource (lib "Miscellaneous Devices") (part "Res1"))
    )
  )
  (nets
    (net (code "1") (name "/switch_led") (class "Default")
      (node (ref "R569") (pin "1") (pinfunction "1_1") (pintype "passive"))
    )
    (net (code "2") (name "GND") (class "Default")
      (node (ref "Q502") (pin "2") (pinfunction "S_2") (pintype "passive"))
      (node (ref "R501") (pin "1") (pinfunction "1_1") (pintype "passive"))
      (node (ref "R502") (pin "1") (pinfunction "1_1") (pintype "passive"))
      (node (ref "R503") (pin "1") (pinfunction "1_1") (pintype "passive"))
      (node (ref "R504") (pin "1") (pinfunction "1_1") (pintype "passive"))
      (node (ref "R505") (pin "1") (pinfunction "1_1") (pintype "passive"))
      (node (ref "R506") (pin "1") (pinfunction "1_1") (pintype "passive"))
      (node (ref "R507") (pin "1") (pinfunction "1_1") (pintype "passive"))
      (node (ref "R508") (pin "1") (pinfunction "1_1") (pintype "passive"))
      (node (ref "R509") (pin "1") (pinfunction "1_1") (pintype "passive"))
      (node (ref "R510") (pin "1") (pinfunction "1_1") (pintype "passive"))
      (node (ref "R511") (pin "1") (pinfunction "1_1") (pintype "passive"))
      (node (ref "R512") (pin "1") (pinfunction "1_1") (pintype "passive"))
      (node (ref "R513") (pin "1") (pinfunction "1_1") (pintype "passive"))
      (node (ref "R514") (pin "1") (pinfunction "1_1") (pintype "passive"))
      (node (ref "R515") (pin "1") (pinfunction "1_1") (pintype "passive"))
      (node (ref "R516") (pin "1") (pinfunction "1_1") (pintype "passive"))
      (node (ref "R517") (pin "1") (pinfunction "1_1") (pintype "passive"))
      (node (ref "R518") (pin "1") (pinfunction "1_1") (pintype "passive"))
      (node (ref "R519") (pin "1") (pinfunction "1_1") (pintype "passive"))
      (node (ref "R520") (pin "1") (pinfunction "1_1") (pintype "passive"))
      (node (ref "R521") (pin "1") (pinfunction "1_1") (pintype "passive"))
      (node (ref "R522") (pin "1") (pinfunction "1_1") (pintype "passive"))
      (node (ref "R523") (pin "1") (pinfunction "1_1") (pintype "passive"))
      (node (ref "R524") (pin "1") (pinfunction "1_1") (pintype "passive"))
      (node (ref "R525") (pin "1") (pinfunction "1_1") (pintype "passive"))
      (node (ref "R526") (pin "1") (pinfunction "1_1") (pintype "passive"))
      (node (ref "R527") (pin "1") (pinfunction "1_1") (pintype "passive"))
      (node (ref "R528_1") (pin "1") (pinfunction "1_1") (pintype "passive"))
      (node (ref "R528_2") (pin "1") (pinfunction "1_1") (pintype "passive"))
      (node (ref "R529") (pin "1") (pinfunction "1_1") (pintype "passive"))
      (node (ref "R530") (pin "1") (pinfunction "1_1") (pintype "passive"))
      (node (ref "R531") (pin "1") (pinfunction "1_1") (pintype "passive"))
      (node (ref "R532") (pin "1") (pinfunction "1_1") (pintype "passive"))
      (node (ref "R533") (pin "1") (pinfunction "1_1") (pintype "passive"))
      (node (ref "R534") (pin "1") (pinfunction "1_1") (pintype "passive"))
      (node (ref "R535") (pin "1") (pinfunction "1_1") (pintype "passive"))
      (node (ref "R536") (pin "1") (pinfunction "1_1") (pintype "passive"))
      (node (ref "R537") (pin "1") (pinfunction "1_1") (pintype "passive"))
      (node (ref "R538") (pin "1") (pinfunction "1_1") (pintype "passive"))
      (node (ref "R539") (pin "1") (pinfunction "1_1") (pintype "passive"))
      (node (ref "R540") (pin "1") (pinfunction "1_1") (pintype "passive"))
      (node (ref "R541") (pin "1") (pinfunction "1_1") (pintype "passive"))
      (node (ref "R542") (pin "1") (pinfunction "1_1") (pintype "passive"))
      (node (ref "R543") (pin "1") (pinfunction "1_1") (pintype "passive"))
      (node (ref "R544") (pin "1") (pinfunction "1_1") (pintype "passive"))
      (node (ref "R545") (pin "1") (pinfunction "1_1") (pintype "passive"))
      (node (ref "R546") (pin "1") (pinfunction "1_1") (pintype "passive"))
      (node (ref "R547") (pin "1") (pinfunction "1_1") (pintype "passive"))
      (node (ref "R548") (pin "1") (pinfunction "1_1") (pintype "passive"))
      (node (ref "R549") (pin "1") (pinfunction "1_1") (pintype "passive"))
      (node (ref "R550") (pin "1") (pinfunction "1_1") (pintype "passive"))
      (node (ref "R551") (pin "1") (pinfunction "1_1") (pintype "passive"))
      (node (ref "R552") (pin "1") (pinfunction "1_1") (pintype "passive"))
      (node (ref "R553") (pin "1") (pinfunction "1_1") (pintype "passive"))
      (node (ref "R554") (pin "1") (pinfunction "1_1") (pintype "passive"))
      (node (ref "R554_2") (pin "1") (pinfunction "1_1") (pintype "passive"))
      (node (ref "R555") (pin "1") (pinfunction "1_1") (pintype "passive"))
      (node (ref "R556") (pin "1") (pinfunction "1_1") (pintype "passive"))
      (node (ref "R556_2") (pin "1") (pinfunction "1_1") (pintype "passive"))
      (node (ref "R557") (pin "1") (pinfunction "1_1") (pintype "passive"))
      (node (ref "R558") (pin "1") (pinfunction "1_1") (pintype "passive"))
      (node (ref "R559") (pin "1") (pinfunction "1_1") (pintype "passive"))
      (node (ref "R561_1") (pin "1") (pinfunction "1_1") (pintype "passive"))
      (node (ref "R561_2") (pin "1") (pinfunction "1_1") (pintype "passive"))
      (node (ref "R563") (pin "1") (pinfunction "1_1") (pintype "passive"))
      (node (ref "R565") (pin "1") (pinfunction "1_1") (pintype "passive"))
      (node (ref "R566") (pin "1") (pinfunction "1_1") (pintype "passive"))
      (node (ref "R567_1") (pin "1") (pinfunction "1_1") (pintype "passive"))
      (node (ref "R567_2") (pin "1") (pinfunction "1_1") (pintype "passive"))
      (node (ref "R570") (pin "2") (pinfunction "2_2") (pintype "passive"))
      (node (ref "R654") (pin "1") (pinfunction "1_1") (pintype "passive"))
    )
    (net (code "3") (name "Net-(D501-K)") (class "Default")
      (node (ref "D501") (pin "2") (pinfunction "K_2") (pintype "passive"))
      (node (ref "R501") (pin "2") (pinfunction "2_2") (pintype "passive"))
    )
    (net (code "4") (name "Net-(D502-K)") (class "Default")
      (node (ref "D502") (pin "2") (pinfunction "K_2") (pintype "passive"))
      (node (ref "R502") (pin "2") (pinfunction "2_2") (pintype "passive"))
    )
    (net (code "5") (name "Net-(D503-K)") (class "Default")
      (node (ref "D503") (pin "2") (pinfunction "K_2") (pintype "passive"))
      (node (ref "R503") (pin "2") (pinfunction "2_2") (pintype "passive"))
    )
    (net (code "6") (name "Net-(D504-K)") (class "Default")
      (node (ref "D504") (pin "2") (pinfunction "K_2") (pintype "passive"))
      (node (ref "R504") (pin "2") (pinfunction "2_2") (pintype "passive"))
    )
    (net (code "7") (name "Net-(D505-K)") (class "Default")
      (node (ref "D505") (pin "2") (pinfunction "K_2") (pintype "passive"))
      (node (ref "R505") (pin "2") (pinfunction "2_2") (pintype "passive"))
    )
    (net (code "8") (name "Net-(D506-K)") (class "Default")
      (node (ref "D506") (pin "2") (pinfunction "K_2") (pintype "passive"))
      (node (ref "R506") (pin "2") (pinfunction "2_2") (pintype "passive"))
    )
    (net (code "9") (name "Net-(D507-K)") (class "Default")
      (node (ref "D507") (pin "2") (pinfunction "K_2") (pintype "passive"))
      (node (ref "R507") (pin "2") (pinfunction "2_2") (pintype "passive"))
    )
    (net (code "10") (name "Net-(D508-K)") (class "Default")
      (node (ref "D508") (pin "2") (pinfunction "K_2") (pintype "passive"))
      (node (ref "R508") (pin "2") (pinfunction "2_2") (pintype "passive"))
    )
    (net (code "11") (name "Net-(D509-K)") (class "Default")
      (node (ref "D509") (pin "2") (pinfunction "K_2") (pintype "passive"))
      (node (ref "R509") (pin "2") (pinfunction "2_2") (pintype "passive"))
    )
    (net (code "12") (name "Net-(D510-K)") (class "Default")
      (node (ref "D510") (pin "2") (pinfunction "K_2") (pintype "passive"))
      (node (ref "R510") (pin "2") (pinfunction "2_2") (pintype "passive"))
    )
    (net (code "13") (name "Net-(D511-K)") (class "Default")
      (node (ref "D511") (pin "2") (pinfunction "K_2") (pintype "passive"))
      (node (ref "R511") (pin "2") (pinfunction "2_2") (pintype "passive"))
    )
    (net (code "14") (name "Net-(D512-K)") (class "Default")
      (node (ref "D512") (pin "2") (pinfunction "K_2") (pintype "passive"))
      (node (ref "R512") (pin "2") (pinfunction "2_2") (pintype "passive"))
    )
    (net (code "15") (name "Net-(D513-K)") (class "Default")
      (node (ref "D513") (pin "2") (pinfunction "K_2") (pintype "passive"))
      (node (ref "R513") (pin "2") (pinfunction "2_2") (pintype "passive"))
    )
    (net (code "16") (name "Net-(D514-K)") (class "Default")
      (node (ref "D514") (pin "2") (pinfunction "K_2") (pintype "passive"))
      (node (ref "R514") (pin "2") (pinfunction "2_2") (pintype "passive"))
    )
    (net (code "17") (name "Net-(D515-K)") (class "Default")
      (node (ref "D515") (pin "2") (pinfunction "K_2") (pintype "passive"))
      (node (ref "R515") (pin "2") (pinfunction "2_2") (pintype "passive"))
    )
    (net (code "18") (name "Net-(D516-K)") (class "Default")
      (node (ref "D516") (pin "2") (pinfunction "K_2") (pintype "passive"))
      (node (ref "R516") (pin "2") (pinfunction "2_2") (pintype "passive"))
    )
    (net (code "19") (name "Net-(D517-K)") (class "Default")
      (node (ref "D517") (pin "2") (pinfunction "K_2") (pintype "passive"))
      (node (ref "R517") (pin "2") (pinfunction "2_2") (pintype "passive"))
    )
    (net (code "20") (name "Net-(D518-K)") (class "Default")
      (node (ref "D518") (pin "2") (pinfunction "K_2") (pintype "passive"))
      (node (ref "R518") (pin "2") (pinfunction "2_2") (pintype "passive"))
    )
    (net (code "21") (name "Net-(D519-K)") (class "Default")
      (node (ref "D519") (pin "2") (pinfunction "K_2") (pintype "passive"))
      (node (ref "R519") (pin "2") (pinfunction "2_2") (pintype "passive"))
    )
    (net (code "22") (name "Net-(D520-K)") (class "Default")
      (node (ref "D520") (pin "2") (pinfunction "K_2") (pintype "passive"))
      (node (ref "R520") (pin "2") (pinfunction "2_2") (pintype "passive"))
    )
    (net (code "23") (name "Net-(D521-K)") (class "Default")
      (node (ref "D521") (pin "2") (pinfunction "K_2") (pintype "passive"))
      (node (ref "R521") (pin "2") (pinfunction "2_2") (pintype "passive"))
    )
    (net (code "24") (name "Net-(D522-K)") (class "Default")
      (node (ref "D522") (pin "2") (pinfunction "K_2") (pintype "passive"))
      (node (ref "R522") (pin "2") (pinfunction "2_2") (pintype "passive"))
    )
    (net (code "25") (name "Net-(D523-K)") (class "Default")
      (node (ref "D523") (pin "2") (pinfunction "K_2") (pintype "passive"))
      (node (ref "R523") (pin "2") (pinfunction "2_2") (pintype "passive"))
    )
    (net (code "26") (name "Net-(D524-K)") (class "Default")
      (node (ref "D524") (pin "2") (pinfunction "K_2") (pintype "passive"))
      (node (ref "R524") (pin "2") (pinfunction "2_2") (pintype "passive"))
    )
    (net (code "27") (name "Net-(D525-K)") (class "Default")
      (node (ref "D525") (pin "2") (pinfunction "K_2") (pintype "passive"))
      (node (ref "R525") (pin "2") (pinfunction "2_2") (pintype "passive"))
    )
    (net (code "28") (name "Net-(D526-K)") (class "Default")
      (node (ref "D526") (pin "2") (pinfunction "K_2") (pintype "passive"))
      (node (ref "R526") (pin "2") (pinfunction "2_2") (pintype "passive"))
    )
    (net (code "29") (name "Net-(D527-K)") (class "Default")
      (node (ref "D527") (pin "2") (pinfunction "K_2") (pintype "passive"))
      (node (ref "R527") (pin "2") (pinfunction "2_2") (pintype "passive"))
    )
    (net (code "30") (name "Net-(D528_1-K)") (class "Default")
      (node (ref "D528_1") (pin "2") (pinfunction "K_2") (pintype "passive"))
      (node (ref "R528_1") (pin "2") (pinfunction "2_2") (pintype "passive"))
    )
    (net (code "31") (name "Net-(D528_2-K)") (class "Default")
      (node (ref "D528_2") (pin "2") (pinfunction "K_2") (pintype "passive"))
      (node (ref "R528_2") (pin "2") (pinfunction "2_2") (pintype "passive"))
    )
    (net (code "32") (name "Net-(D529-K)") (class "Default")
      (node (ref "D529") (pin "2") (pinfunction "K_2") (pintype "passive"))
      (node (ref "R529") (pin "2") (pinfunction "2_2") (pintype "passive"))
    )
    (net (code "33") (name "Net-(D530-K)") (class "Default")
      (node (ref "D530") (pin "2") (pinfunction "K_2") (pintype "passive"))
      (node (ref "R530") (pin "2") (pinfunction "2_2") (pintype "passive"))
    )
    (net (code "34") (name "Net-(D531-K)") (class "Default")
      (node (ref "D531") (pin "2") (pinfunction "K_2") (pintype "passive"))
      (node (ref "R531") (pin "2") (pinfunction "2_2") (pintype "passive"))
    )
    (net (code "35") (name "Net-(D532-K)") (class "Default")
      (node (ref "D532") (pin "2") (pinfunction "K_2") (pintype "passive"))
      (node (ref "R532") (pin "2") (pinfunction "2_2") (pintype "passive"))
    )
    (net (code "36") (name "Net-(D533-K)") (class "Default")
      (node (ref "D533") (pin "2") (pinfunction "K_2") (pintype "passive"))
      (node (ref "R533") (pin "2") (pinfunction "2_2") (pintype "passive"))
    )
    (net (code "37") (name "Net-(D534-K)") (class "Default")
      (node (ref "D534") (pin "2") (pinfunction "K_2") (pintype "passive"))
      (node (ref "R534") (pin "2") (pinfunction "2_2") (pintype "passive"))
    )
    (net (code "38") (name "Net-(D535-K)") (class "Default")
      (node (ref "D535") (pin "2") (pinfunction "K_2") (pintype "passive"))
      (node (ref "R535") (pin "2") (pinfunction "2_2") (pintype "passive"))
    )
    (net (code "39") (name "Net-(D536-K)") (class "Default")
      (node (ref "D536") (pin "2") (pinfunction "K_2") (pintype "passive"))
      (node (ref "R536") (pin "2") (pinfunction "2_2") (pintype "passive"))
    )
    (net (code "40") (name "Net-(D537-K)") (class "Default")
      (node (ref "D537") (pin "2") (pinfunction "K_2") (pintype "passive"))
      (node (ref "R537") (pin "2") (pinfunction "2_2") (pintype "passive"))
    )
    (net (code "41") (name "Net-(D538-K)") (class "Default")
      (node (ref "D538") (pin "2") (pinfunction "K_2") (pintype "passive"))
      (node (ref "R538") (pin "2") (pinfunction "2_2") (pintype "passive"))
    )
    (net (code "42") (name "Net-(D539-K)") (class "Default")
      (node (ref "D539") (pin "2") (pinfunction "K_2") (pintype "passive"))
      (node (ref "R539") (pin "2") (pinfunction "2_2") (pintype "passive"))
    )
    (net (code "43") (name "Net-(D540-K)") (class "Default")
      (node (ref "D540") (pin "2") (pinfunction "K_2") (pintype "passive"))
      (node (ref "R540") (pin "2") (pinfunction "2_2") (pintype "passive"))
    )
    (net (code "44") (name "Net-(D541-K)") (class "Default")
      (node (ref "D541") (pin "2") (pinfunction "K_2") (pintype "passive"))
      (node (ref "R541") (pin "2") (pinfunction "2_2") (pintype "passive"))
    )
    (net (code "45") (name "Net-(D542-K)") (class "Default")
      (node (ref "D542") (pin "2") (pinfunction "K_2") (pintype "passive"))
      (node (ref "R542") (pin "2") (pinfunction "2_2") (pintype "passive"))
    )
    (net (code "46") (name "Net-(D543-K)") (class "Default")
      (node (ref "D543") (pin "2") (pinfunction "K_2") (pintype "passive"))
      (node (ref "R543") (pin "2") (pinfunction "2_2") (pintype "passive"))
    )
    (net (code "47") (name "Net-(D544_1-K)") (class "Default")
      (node (ref "D544_1") (pin "2") (pinfunction "K_2") (pintype "passive"))
      (node (ref "R544") (pin "2") (pinfunction "2_2") (pintype "passive"))
    )
    (net (code "48") (name "Net-(D544_2-K)") (class "Default")
      (node (ref "D544_2") (pin "2") (pinfunction "K_2") (pintype "passive"))
      (node (ref "R554_2") (pin "2") (pinfunction "2_2") (pintype "passive"))
    )
    (net (code "49") (name "Net-(D545-K)") (class "Default")
      (node (ref "D545") (pin "2") (pinfunction "K_2") (pintype "passive"))
      (node (ref "R545") (pin "2") (pinfunction "2_2") (pintype "passive"))
    )
    (net (code "50") (name "Net-(D546-K)") (class "Default")
      (node (ref "D546") (pin "2") (pinfunction "K_2") (pintype "passive"))
      (node (ref "R546") (pin "2") (pinfunction "2_2") (pintype "passive"))
    )
    (net (code "51") (name "Net-(D547-K)") (class "Default")
      (node (ref "D547") (pin "2") (pinfunction "K_2") (pintype "passive"))
      (node (ref "R547") (pin "2") (pinfunction "2_2") (pintype "passive"))
    )
    (net (code "52") (name "Net-(D548-K)") (class "Default")
      (node (ref "D548") (pin "2") (pinfunction "K_2") (pintype "passive"))
      (node (ref "R548") (pin "2") (pinfunction "2_2") (pintype "passive"))
    )
    (net (code "53") (name "Net-(D549-K)") (class "Default")
      (node (ref "D549") (pin "2") (pinfunction "K_2") (pintype "passive"))
      (node (ref "R549") (pin "2") (pinfunction "2_2") (pintype "passive"))
    )
    (net (code "54") (name "Net-(D550-K)") (class "Default")
      (node (ref "D550") (pin "2") (pinfunction "K_2") (pintype "passive"))
      (node (ref "R550") (pin "2") (pinfunction "2_2") (pintype "passive"))
    )
    (net (code "55") (name "Net-(D551-K)") (class "Default")
      (node (ref "D551") (pin "2") (pinfunction "K_2") (pintype "passive"))
      (node (ref "R551") (pin "2") (pinfunction "2_2") (pintype "passive"))
    )
    (net (code "56") (name "Net-(D552-K)") (class "Default")
      (node (ref "D552") (pin "2") (pinfunction "K_2") (pintype "passive"))
      (node (ref "R552") (pin "2") (pinfunction "2_2") (pintype "passive"))
    )
    (net (code "57") (name "Net-(D553-K)") (class "Default")
      (node (ref "D553") (pin "2") (pinfunction "K_2") (pintype "passive"))
      (node (ref "R553") (pin "2") (pinfunction "2_2") (pintype "passive"))
    )
    (net (code "58") (name "Net-(D554-K)") (class "Default")
      (node (ref "D554") (pin "2") (pinfunction "K_2") (pintype "passive"))
      (node (ref "R554") (pin "2") (pinfunction "2_2") (pintype "passive"))
    )
    (net (code "59") (name "Net-(D555-K)") (class "Default")
      (node (ref "D555") (pin "2") (pinfunction "K_2") (pintype "passive"))
      (node (ref "R555") (pin "2") (pinfunction "2_2") (pintype "passive"))
    )
    (net (code "60") (name "Net-(D556_1-K)") (class "Default")
      (node (ref "D556_1") (pin "2") (pinfunction "K_2") (pintype "passive"))
      (node (ref "R556") (pin "2") (pinfunction "2_2") (pintype "passive"))
    )
    (net (code "61") (name "Net-(D556_2-K)") (class "Default")
      (node (ref "D556_2") (pin "2") (pinfunction "K_2") (pintype "passive"))
      (node (ref "R556_2") (pin "2") (pinfunction "2_2") (pintype "passive"))
    )
    (net (code "62") (name "Net-(D557-K)") (class "Default")
      (node (ref "D557") (pin "2") (pinfunction "K_2") (pintype "passive"))
      (node (ref "R557") (pin "2") (pinfunction "2_2") (pintype "passive"))
    )
    (net (code "63") (name "Net-(D558-K)") (class "Default")
      (node (ref "D558") (pin "2") (pinfunction "K_2") (pintype "passive"))
      (node (ref "R558") (pin "2") (pinfunction "2_2") (pintype "passive"))
    )
    (net (code "64") (name "Net-(D559-K)") (class "Default")
      (node (ref "D559") (pin "2") (pinfunction "K_2") (pintype "passive"))
      (node (ref "R559") (pin "2") (pinfunction "2_2") (pintype "passive"))
    )
    (net (code "65") (name "Net-(D561_1-K)") (class "Default")
      (node (ref "D561_1") (pin "2") (pinfunction "K_2") (pintype "passive"))
      (node (ref "R561_1") (pin "2") (pinfunction "2_2") (pintype "passive"))
    )
    (net (code "66") (name "Net-(D561_2-K)") (class "Default")
      (node (ref "D561_2") (pin "2") (pinfunction "K_2") (pintype "passive"))
      (node (ref "R561_2") (pin "2") (pinfunction "2_2") (pintype "passive"))
    )
    (net (code "67") (name "Net-(D563-K)") (class "Default")
      (node (ref "D563") (pin "2") (pinfunction "K_2") (pintype "passive"))
      (node (ref "R563") (pin "2") (pinfunction "2_2") (pintype "passive"))
    )
    (net (code "68") (name "Net-(D564-K)") (class "Default")
      (node (ref "D564") (pin "2") (pinfunction "K_2") (pintype "passive"))
      (node (ref "R654") (pin "2") (pinfunction "2_2") (pintype "passive"))
    )
    (net (code "69") (name "Net-(D565-K)") (class "Default")
      (node (ref "D565") (pin "2") (pinfunction "K_2") (pintype "passive"))
      (node (ref "R565") (pin "2") (pinfunction "2_2") (pintype "passive"))
    )
    (net (code "70") (name "Net-(D566-K)") (class "Default")
      (node (ref "D566") (pin "2") (pinfunction "K_2") (pintype "passive"))
      (node (ref "R566") (pin "2") (pinfunction "2_2") (pintype "passive"))
    )
    (net (code "71") (name "Net-(D567_1-K)") (class "Default")
      (node (ref "D567_1") (pin "2") (pinfunction "K_2") (pintype "passive"))
      (node (ref "R567_1") (pin "2") (pinfunction "2_2") (pintype "passive"))
    )
    (net (code "72") (name "Net-(D567_2-K)") (class "Default")
      (node (ref "D567_2") (pin "2") (pinfunction "K_2") (pintype "passive"))
      (node (ref "R567_2") (pin "2") (pinfunction "2_2") (pintype "passive"))
    )
    (net (code "73") (name "Net-(Q501-G)") (class "Default")
      (node (ref "Q501") (pin "1") (pinfunction "G_1") (pintype "passive"))
      (node (ref "Q502") (pin "3") (pinfunction "D_3") (pintype "passive"))
      (node (ref "R568") (pin "1") (pinfunction "1_1") (pintype "passive"))
    )
    (net (code "74") (name "Net-(Q502-G)") (class "Default")
      (node (ref "Q502") (pin "1") (pinfunction "G_1") (pintype "passive"))
      (node (ref "R569") (pin "2") (pinfunction "2_2") (pintype "passive"))
      (node (ref "R570") (pin "1") (pinfunction "1_1") (pintype "passive"))
    )
    (net (code "75") (name "VCC5V") (class "Default")
      (node (ref "Q501") (pin "2") (pinfunction "S_2") (pintype "passive"))
      (node (ref "R568") (pin "2") (pinfunction "2_2") (pintype "passive"))
    )
    (net (code "76") (name "VCC_EXT") (class "Default")
      (node (ref "D501") (pin "1") (pinfunction "A_1") (pintype "passive"))
      (node (ref "D502") (pin "1") (pinfunction "A_1") (pintype "passive"))
      (node (ref "D503") (pin "1") (pinfunction "A_1") (pintype "passive"))
      (node (ref "D504") (pin "1") (pinfunction "A_1") (pintype "passive"))
      (node (ref "D505") (pin "1") (pinfunction "A_1") (pintype "passive"))
      (node (ref "D506") (pin "1") (pinfunction "A_1") (pintype "passive"))
      (node (ref "D507") (pin "1") (pinfunction "A_1") (pintype "passive"))
      (node (ref "D508") (pin "1") (pinfunction "A_1") (pintype "passive"))
      (node (ref "D509") (pin "1") (pinfunction "A_1") (pintype "passive"))
      (node (ref "D510") (pin "1") (pinfunction "A_1") (pintype "passive"))
      (node (ref "D511") (pin "1") (pinfunction "A_1") (pintype "passive"))
      (node (ref "D512") (pin "1") (pinfunction "A_1") (pintype "passive"))
      (node (ref "D513") (pin "1") (pinfunction "A_1") (pintype "passive"))
      (node (ref "D514") (pin "1") (pinfunction "A_1") (pintype "passive"))
      (node (ref "D515") (pin "1") (pinfunction "A_1") (pintype "passive"))
      (node (ref "D516") (pin "1") (pinfunction "A_1") (pintype "passive"))
      (node (ref "D517") (pin "1") (pinfunction "A_1") (pintype "passive"))
      (node (ref "D518") (pin "1") (pinfunction "A_1") (pintype "passive"))
      (node (ref "D519") (pin "1") (pinfunction "A_1") (pintype "passive"))
      (node (ref "D520") (pin "1") (pinfunction "A_1") (pintype "passive"))
      (node (ref "D521") (pin "1") (pinfunction "A_1") (pintype "passive"))
      (node (ref "D522") (pin "1") (pinfunction "A_1") (pintype "passive"))
      (node (ref "D523") (pin "1") (pinfunction "A_1") (pintype "passive"))
      (node (ref "D524") (pin "1") (pinfunction "A_1") (pintype "passive"))
      (node (ref "D525") (pin "1") (pinfunction "A_1") (pintype "passive"))
      (node (ref "D526") (pin "1") (pinfunction "A_1") (pintype "passive"))
      (node (ref "D527") (pin "1") (pinfunction "A_1") (pintype "passive"))
      (node (ref "D528_1") (pin "1") (pinfunction "A_1") (pintype "passive"))
      (node (ref "D528_2") (pin "1") (pinfunction "A_1") (pintype "passive"))
      (node (ref "D529") (pin "1") (pinfunction "A_1") (pintype "passive"))
      (node (ref "D530") (pin "1") (pinfunction "A_1") (pintype "passive"))
      (node (ref "D531") (pin "1") (pinfunction "A_1") (pintype "passive"))
      (node (ref "D532") (pin "1") (pinfunction "A_1") (pintype "passive"))
      (node (ref "D533") (pin "1") (pinfunction "A_1") (pintype "passive"))
      (node (ref "D534") (pin "1") (pinfunction "A_1") (pintype "passive"))
      (node (ref "D535") (pin "1") (pinfunction "A_1") (pintype "passive"))
      (node (ref "D536") (pin "1") (pinfunction "A_1") (pintype "passive"))
      (node (ref "D537") (pin "1") (pinfunction "A_1") (pintype "passive"))
      (node (ref "D538") (pin "1") (pinfunction "A_1") (pintype "passive"))
      (node (ref "D539") (pin "1") (pinfunction "A_1") (pintype "passive"))
      (node (ref "D540") (pin "1") (pinfunction "A_1") (pintype "passive"))
      (node (ref "D541") (pin "1") (pinfunction "A_1") (pintype "passive"))
      (node (ref "D542") (pin "1") (pinfunction "A_1") (pintype "passive"))
      (node (ref "D543") (pin "1") (pinfunction "A_1") (pintype "passive"))
      (node (ref "D544_1") (pin "1") (pinfunction "A_1") (pintype "passive"))
      (node (ref "D544_2") (pin "1") (pinfunction "A_1") (pintype "passive"))
      (node (ref "D545") (pin "1") (pinfunction "A_1") (pintype "passive"))
      (node (ref "D546") (pin "1") (pinfunction "A_1") (pintype "passive"))
      (node (ref "D547") (pin "1") (pinfunction "A_1") (pintype "passive"))
      (node (ref "D548") (pin "1") (pinfunction "A_1") (pintype "passive"))
      (node (ref "D549") (pin "1") (pinfunction "A_1") (pintype "passive"))
      (node (ref "D550") (pin "1") (pinfunction "A_1") (pintype "passive"))
      (node (ref "D551") (pin "1") (pinfunction "A_1") (pintype "passive"))
      (node (ref "D552") (pin "1") (pinfunction "A_1") (pintype "passive"))
      (node (ref "D553") (pin "1") (pinfunction "A_1") (pintype "passive"))
      (node (ref "D554") (pin "1") (pinfunction "A_1") (pintype "passive"))
      (node (ref "D555") (pin "1") (pinfunction "A_1") (pintype "passive"))
      (node (ref "D556_1") (pin "1") (pinfunction "A_1") (pintype "passive"))
      (node (ref "D556_2") (pin "1") (pinfunction "A_1") (pintype "passive"))
      (node (ref "D557") (pin "1") (pinfunction "A_1") (pintype "passive"))
      (node (ref "D558") (pin "1") (pinfunction "A_1") (pintype "passive"))
      (node (ref "D559") (pin "1") (pinfunction "A_1") (pintype "passive"))
      (node (ref "D561_1") (pin "1") (pinfunction "A_1") (pintype "passive"))
      (node (ref "D561_2") (pin "1") (pinfunction "A_1") (pintype "passive"))
      (node (ref "D563") (pin "1") (pinfunction "A_1") (pintype "passive"))
      (node (ref "D564") (pin "1") (pinfunction "A_1") (pintype "passive"))
      (node (ref "D565") (pin "1") (pinfunction "A_1") (pintype "passive"))
      (node (ref "D566") (pin "1") (pinfunction "A_1") (pintype "passive"))
      (node (ref "D567_1") (pin "1") (pinfunction "A_1") (pintype "passive"))
      (node (ref "D567_2") (pin "1") (pinfunction "A_1") (pintype "passive"))
      (node (ref "Q501") (pin "3") (pinfunction "D_3") (pintype "passive"))
    )
  )
)
